# Sheet2.net
KiCad netlist of a schematic drawn in Altium Designer
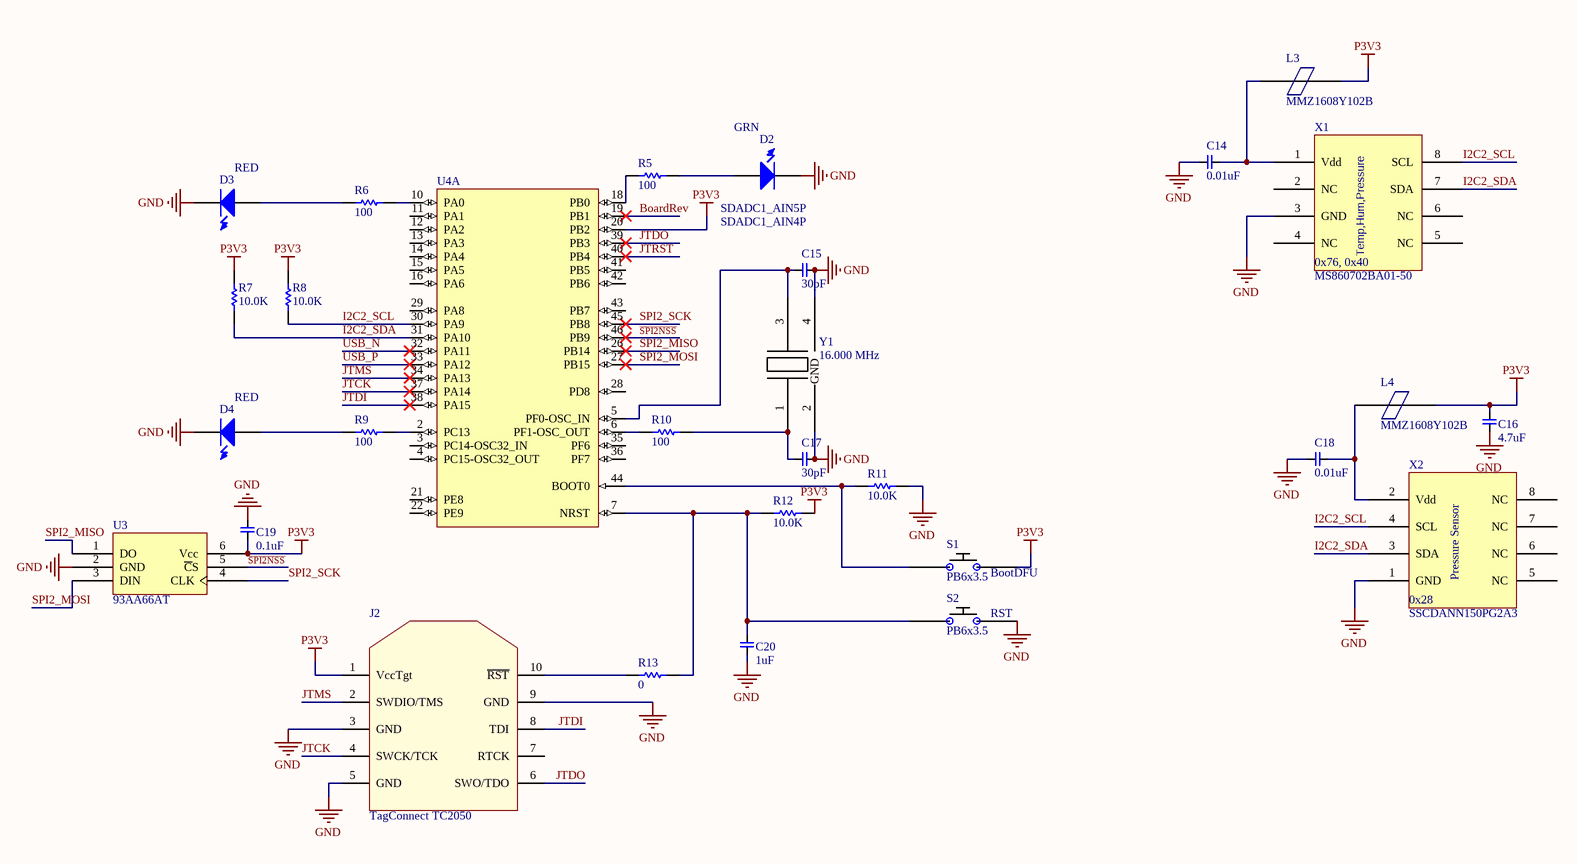
[diagram p0: Sheet2.SchDoc]

(export (version "E")
  (design (tool "Eeschema 10.0.6"))
  (components
    (comp (ref "C14")
      (value "0.01uF")
      (footprint "CAP0402")
      (description "CAP 0.01uF +/-20% 50V X6S 0402")
      (fields (field (name "TOLERANCE") "+/-20%") (field (name "VOLTAGE") "50V"))
      (libsource (lib "PassiveSMT") (part "Capacitor_np"))
    )
    (comp (ref "C15")
      (value "30pF")
      (footprint "CAP0402")
      (description "CAP 30pF +/-5% 50V C0G 0402")
      (fields (field (name "TOLERANCE") "+/-5%") (field (name "VOLTAGE") "50V"))
      (libsource (lib "PassiveSMT") (part "Capacitor_np"))
    )
    (comp (ref "C16")
      (value "4.7uF")
      (footprint "CAP0603")
      (description "CAP 4.7uF +/-10% 10V X6S 0603")
      (fields (field (name "TOLERANCE") "+/-10%") (field (name "VOLTAGE") "10V"))
      (libsource (lib "PassiveSMT") (part "Capacitor_np"))
    )
    (comp (ref "C17")
      (value "30pF")
      (footprint "CAP0402")
      (description "CAP 30pF +/-5% 50V C0G 0402")
      (fields (field (name "TOLERANCE") "+/-5%") (field (name "VOLTAGE") "50V"))
      (libsource (lib "PassiveSMT") (part "Capacitor_np"))
    )
    (comp (ref "C18")
      (value "0.01uF")
      (footprint "CAP0402")
      (description "CAP 0.01uF +/-20% 50V X6S 0402")
      (fields (field (name "TOLERANCE") "+/-20%") (field (name "VOLTAGE") "50V"))
      (libsource (lib "PassiveSMT") (part "Capacitor_np"))
    )
    (comp (ref "C19")
      (value "0.1uF")
      (footprint "CAP0402")
      (description "CAP 0.1uF +/-10% 25V X7R 0402")
      (fields (field (name "TOLERANCE") "+/-10%") (field (name "VOLTAGE") "25V"))
      (libsource (lib "PassiveSMT") (part "Capacitor_np"))
    )
    (comp (ref "C20")
      (value "1uF")
      (footprint "CAP0402")
      (description "CAP 1uF +/-10% 10V X5R 0402")
      (fields (field (name "TOLERANCE") "+/-10%") (field (name "VOLTAGE") "10V"))
      (libsource (lib "PassiveSMT") (part "Capacitor_np"))
    )
    (comp (ref "D2")
      (value "GRN")
      (footprint "KINGBRIGHT_LED")
      (description "LED 1.6X0.8MM 568NM GRN CLR SMD")
      (fields (field (name "MANUFACTURER") "Kingbright"))
      (libsource (lib "MF_MiscLib") (part "LED_GRN_SMD_0603"))
    )
    (comp (ref "D3")
      (value "RED")
      (footprint "KINGBRIGHT_LED")
      (description "LED 1.6X0.8MM 630NM RED CLR SMD")
      (fields (field (name "MANUFACTURER") "Kingbright"))
      (libsource (lib "MF_MiscLib") (part "LED_RED_SMD_0603"))
    )
    (comp (ref "D4")
      (value "RED")
      (footprint "KINGBRIGHT_LED")
      (description "LED 1.6X0.8MM 630NM RED CLR SMD")
      (fields (field (name "MANUFACTURER") "Kingbright"))
      (libsource (lib "MF_MiscLib") (part "LED_RED_SMD_0603"))
    )
    (comp (ref "J2")
      (value "TagConnect TC2050")
      (footprint "TC2050-IDC")
      (description "TagConnect TC2050-IDC For ARM JTAG")
      (fields (field (name "MANUFACTURER") "Tag-Connect LLC"))
      (libsource (lib "MF_MiscLib") (part "TC2050_ARMJTAG"))
    )
    (comp (ref "L3")
      (value "MMZ1608Y102B")
      (footprint "INDC1608X06N")
      (description "Ferrite, 1000oh, 400mA, 0603")
      (libsource (lib "MF_MiscLib") (part "MMZ1608Y102B"))
    )
    (comp (ref "L4")
      (value "MMZ1608Y102B")
      (footprint "INDC1608X06N")
      (description "Ferrite, 1000oh, 400mA, 0603")
      (libsource (lib "MF_MiscLib") (part "MMZ1608Y102B"))
    )
    (comp (ref "R5")
      (value "100")
      (footprint "RES0402")
      (description "Resistor SMT 0402 100 1% ohm")
      (fields (field (name "TOLERANCE") "1%") (field (name "POWER") "1/16W"))
      (libsource (lib "PassiveSMT") (part "Resistor1"))
    )
    (comp (ref "R6")
      (value "100")
      (footprint "RES0402")
      (description "Resistor SMT 0402 100 1% ohm")
      (fields (field (name "TOLERANCE") "1%") (field (name "POWER") "1/16W"))
      (libsource (lib "PassiveSMT") (part "Resistor1"))
    )
    (comp (ref "R7")
      (value "10.0K")
      (footprint "RES0402")
      (description "Resistor SMT 0402 10.0K 1% ohm")
      (fields (field (name "TOLERANCE") "1%") (field (name "POWER") "1/16W"))
      (libsource (lib "PassiveSMT") (part "Resistor1"))
    )
    (comp (ref "R8")
      (value "10.0K")
      (footprint "RES0402")
      (description "Resistor SMT 0402 10.0K 1% ohm")
      (fields (field (name "TOLERANCE") "1%") (field (name "POWER") "1/16W"))
      (libsource (lib "PassiveSMT") (part "Resistor1"))
    )
    (comp (ref "R9")
      (value "100")
      (footprint "RES0402")
      (description "Resistor SMT 0402 100 1% ohm")
      (fields (field (name "TOLERANCE") "1%") (field (name "POWER") "1/16W"))
      (libsource (lib "PassiveSMT") (part "Resistor1"))
    )
    (comp (ref "R10")
      (value "100")
      (footprint "RES0402")
      (description "Resistor SMT 0402 100 1% ohm")
      (fields (field (name "TOLERANCE") "1%") (field (name "POWER") "1/16W"))
      (libsource (lib "PassiveSMT") (part "Resistor1"))
    )
    (comp (ref "R11")
      (value "10.0K")
      (footprint "RES0402")
      (description "Resistor SMT 0402 10.0K 1% ohm")
      (fields (field (name "TOLERANCE") "1%") (field (name "POWER") "1/16W"))
      (libsource (lib "PassiveSMT") (part "Resistor1"))
    )
    (comp (ref "R12")
      (value "10.0K")
      (footprint "RES0402")
      (description "Resistor SMT 0402 10.0K 1% ohm")
      (fields (field (name "TOLERANCE") "1%") (field (name "POWER") "1/16W"))
      (libsource (lib "PassiveSMT") (part "Resistor1"))
    )
    (comp (ref "R13")
      (value "0")
      (footprint "RES0402")
      (description "Resistor SMT 0402 0 1% ohm")
      (fields (field (name "TOLERANCE") "1%") (field (name "POWER") "1/16W"))
      (libsource (lib "PassiveSMT") (part "Resistor1"))
    )
    (comp (ref "S1")
      (value "PB6x3.5")
      (footprint "PTS635")
      (description "SWITCH TACTILE SPST-NO 0.05A 12V 6x3.5MM")
      (fields (field (name "MANUFACTURER") "C&K Components"))
      (libsource (lib "MF_MiscLib") (part "PushButton_6x3.5mm"))
    )
    (comp (ref "S2")
      (value "PB6x3.5")
      (footprint "PTS635")
      (description "SWITCH TACTILE SPST-NO 0.05A 12V 6x3.5MM")
      (fields (field (name "MANUFACTURER") "C&K Components"))
      (libsource (lib "MF_MiscLib") (part "PushButton_6x3.5mm"))
    )
    (comp (ref "U3")
      (value "93AA66AT")
      (footprint "SOT-23-OT6_M")
      (description "IC EEPROM 4KBIT 2MHZ SOT23-6")
      (fields (field (name "MANUFACTURER") "Microchip Technology"))
      (libsource (lib "MF_MiscLib") (part "93AA66AT_SOT23-6"))
    )
    (comp (ref "U4")
      (value "~")
      (footprint "STM-LQFP48_N")
      (fields (field (name "PARTNUMBER") "STM32F373CCT6"))
      (libsource (lib "STMicroelectronics_STM32_F3") (part "STM32F373CCT6"))
    )
    (comp (ref "X1")
      (value "MS860702BA01-50")
      (footprint "TETempHumidityPressSens")
      (description "Humidity, Pressure, Temperature Sensor I²C Output")
      (fields (field (name "MANUFACTURER") "TE Connectivity"))
      (libsource (lib "MF_MiscLib") (part "MS860702BA01-50"))
    )
    (comp (ref "X2")
      (value "SSCDANN150PG2A3")
      (footprint "HoneywellPsenseDIP")
      (description "SENSOR PRES 150PSI GAUG 3.3V DIP I2C")
      (fields (field (name "MANUFACTURER") "Honeywell"))
      (libsource (lib "MF_MiscLib") (part "SSCDANN150PG2A3"))
    )
    (comp (ref "Y1")
      (value "16.000 MHz")
      (footprint "CRYSTAL_SMD_3.2x2.5")
      (description "CRYSTAL 16.0MHZ 20PF,80ohm PARALLEL SMD +/-10PPM")
      (fields (field (name "MANUFACTURER") "CTS-Frequency Controls"))
      (libsource (lib "MF_MiscLib") (part "Crystal_16.00MHz_SMD"))
    )
  )
  (nets
    (net (code "1") (name "/BoardRev") (class "Default")
      (node (ref "U4") (pin "19") (pinfunction "PB1_19") (pintype "bidirectional+no_connect"))
    )
    (net (code "2") (name "/I2C2_SCL") (class "Default")
      (node (ref "R8") (pin "2") (pinfunction "2_2") (pintype "passive"))
      (node (ref "U4") (pin "30") (pinfunction "PA9_30") (pintype "bidirectional"))
      (node (ref "X1") (pin "8") (pinfunction "SCL_8") (pintype "passive"))
      (node (ref "X2") (pin "4") (pinfunction "SCL_4") (pintype "passive"))
    )
    (net (code "3") (name "/I2C2_SDA") (class "Default")
      (node (ref "R7") (pin "2") (pinfunction "2_2") (pintype "passive"))
      (node (ref "U4") (pin "31") (pinfunction "PA10_31") (pintype "bidirectional"))
      (node (ref "X1") (pin "7") (pinfunction "SDA_7") (pintype "passive"))
      (node (ref "X2") (pin "3") (pinfunction "SDA_3") (pintype "passive"))
    )
    (net (code "4") (name "/JTCK") (class "Default")
      (node (ref "J2") (pin "4") (pinfunction "SWCK/TCK_4") (pintype "passive"))
      (node (ref "U4") (pin "37") (pinfunction "PA14_37") (pintype "bidirectional"))
    )
    (net (code "5") (name "/JTDI") (class "Default")
      (node (ref "J2") (pin "8") (pinfunction "TDI_8") (pintype "passive"))
      (node (ref "U4") (pin "38") (pinfunction "PA15_38") (pintype "bidirectional"))
    )
    (net (code "6") (name "/JTDO") (class "Default")
      (node (ref "J2") (pin "6") (pinfunction "SWO/TDO_6") (pintype "passive"))
      (node (ref "U4") (pin "39") (pinfunction "PB3_39") (pintype "bidirectional"))
    )
    (net (code "7") (name "/JTMS") (class "Default")
      (node (ref "J2") (pin "2") (pinfunction "SWDIO/TMS_2") (pintype "passive"))
      (node (ref "U4") (pin "34") (pinfunction "PA13_34") (pintype "bidirectional"))
    )
    (net (code "8") (name "/JTRST") (class "Default")
      (node (ref "U4") (pin "40") (pinfunction "PB4_40") (pintype "bidirectional+no_connect"))
    )
    (net (code "9") (name "/SPI2NSS") (class "Default")
      (node (ref "U3") (pin "5") (pinfunction "~{C}S_5") (pintype "passive"))
      (node (ref "U4") (pin "46") (pinfunction "PB9_46") (pintype "bidirectional"))
    )
    (net (code "10") (name "/SPI2_MISO") (class "Default")
      (node (ref "U3") (pin "1") (pinfunction "DO_1") (pintype "passive"))
      (node (ref "U4") (pin "26") (pinfunction "PB14_26") (pintype "bidirectional"))
    )
    (net (code "11") (name "/SPI2_MOSI") (class "Default")
      (node (ref "U3") (pin "3") (pinfunction "DIN_3") (pintype "passive"))
      (node (ref "U4") (pin "27") (pinfunction "PB15_27") (pintype "bidirectional"))
    )
    (net (code "12") (name "/SPI2_SCK") (class "Default")
      (node (ref "U3") (pin "4") (pinfunction "CLK_4") (pintype "passive"))
      (node (ref "U4") (pin "45") (pinfunction "PB8_45") (pintype "bidirectional"))
    )
    (net (code "13") (name "/USB_N") (class "Default")
      (node (ref "U4") (pin "32") (pinfunction "PA11_32") (pintype "bidirectional+no_connect"))
    )
    (net (code "14") (name "/USB_P") (class "Default")
      (node (ref "U4") (pin "33") (pinfunction "PA12_33") (pintype "bidirectional+no_connect"))
    )
    (net (code "15") (name "GND") (class "Default")
      (node (ref "C14") (pin "2") (pinfunction "2_2") (pintype "passive"))
      (node (ref "C15") (pin "1") (pinfunction "1_1") (pintype "passive"))
      (node (ref "C16") (pin "2") (pinfunction "2_2") (pintype "passive"))
      (node (ref "C17") (pin "1") (pinfunction "1_1") (pintype "passive"))
      (node (ref "C18") (pin "2") (pinfunction "2_2") (pintype "passive"))
      (node (ref "C19") (pin "2") (pinfunction "2_2") (pintype "passive"))
      (node (ref "C20") (pin "1") (pinfunction "1_1") (pintype "passive"))
      (node (ref "D2") (pin "2") (pinfunction "K_2") (pintype "passive"))
      (node (ref "D3") (pin "2") (pinfunction "K_2") (pintype "passive"))
      (node (ref "D4") (pin "2") (pinfunction "K_2") (pintype "passive"))
      (node (ref "J2") (pin "3") (pinfunction "GND_3") (pintype "passive"))
      (node (ref "J2") (pin "5") (pinfunction "GND_5") (pintype "passive"))
      (node (ref "J2") (pin "9") (pinfunction "GND_9") (pintype "passive"))
      (node (ref "R11") (pin "2") (pinfunction "2_2") (pintype "passive"))
      (node (ref "S2") (pin "2") (pinfunction "2_2") (pintype "passive"))
      (node (ref "U3") (pin "2") (pinfunction "GND_2") (pintype "passive"))
      (node (ref "X1") (pin "3") (pinfunction "GND_3") (pintype "passive"))
      (node (ref "X2") (pin "1") (pinfunction "GND_1") (pintype "passive"))
      (node (ref "Y1") (pin "2") (pinfunction "GND_2") (pintype "passive"))
      (node (ref "Y1") (pin "4") (pinfunction "4_4") (pintype "passive"))
    )
    (net (code "16") (name "Net-(C17-Pad2)") (class "Default")
      (node (ref "C17") (pin "2") (pinfunction "2_2") (pintype "passive"))
      (node (ref "R10") (pin "2") (pinfunction "2_2") (pintype "passive"))
      (node (ref "Y1") (pin "1") (pinfunction "1_1") (pintype "passive"))
    )
    (net (code "17") (name "Net-(D2-A)") (class "Default")
      (node (ref "D2") (pin "1") (pinfunction "A_1") (pintype "passive"))
      (node (ref "R5") (pin "2") (pinfunction "2_2") (pintype "passive"))
    )
    (net (code "18") (name "Net-(D3-A)") (class "Default")
      (node (ref "D3") (pin "1") (pinfunction "A_1") (pintype "passive"))
      (node (ref "R6") (pin "1") (pinfunction "1_1") (pintype "passive"))
    )
    (net (code "19") (name "Net-(D4-A)") (class "Default")
      (node (ref "D4") (pin "1") (pinfunction "A_1") (pintype "passive"))
      (node (ref "R9") (pin "1") (pinfunction "1_1") (pintype "passive"))
    )
    (net (code "20") (name "Net-(J2-RST)") (class "Default")
      (node (ref "J2") (pin "10") (pinfunction "RST_10") (pintype "passive"))
      (node (ref "R13") (pin "1") (pinfunction "1_1") (pintype "passive"))
    )
    (net (code "21") (name "Net-(U4A-BOOT0)") (class "Default")
      (node (ref "R11") (pin "1") (pinfunction "1_1") (pintype "passive"))
      (node (ref "S1") (pin "1") (pinfunction "1_1") (pintype "passive"))
      (node (ref "U4") (pin "44") (pinfunction "BOOT0_44") (pintype "input"))
    )
    (net (code "22") (name "Net-(U4A-NRST)") (class "Default")
      (node (ref "C20") (pin "2") (pinfunction "2_2") (pintype "passive"))
      (node (ref "R12") (pin "1") (pinfunction "1_1") (pintype "passive"))
      (node (ref "R13") (pin "2") (pinfunction "2_2") (pintype "passive"))
      (node (ref "S2") (pin "1") (pinfunction "1_1") (pintype "passive"))
      (node (ref "U4") (pin "7") (pinfunction "NRST_7") (pintype "bidirectional"))
    )
    (net (code "23") (name "Net-(U4A-PA0)") (class "Default")
      (node (ref "R6") (pin "2") (pinfunction "2_2") (pintype "passive"))
      (node (ref "U4") (pin "10") (pinfunction "PA0_10") (pintype "bidirectional"))
    )
    (net (code "24") (name "Net-(U4A-PB0)") (class "Default")
      (node (ref "R5") (pin "1") (pinfunction "1_1") (pintype "passive"))
      (node (ref "U4") (pin "18") (pinfunction "PB0_18") (pintype "bidirectional"))
    )
    (net (code "25") (name "Net-(U4A-PC13)") (class "Default")
      (node (ref "R9") (pin "2") (pinfunction "2_2") (pintype "passive"))
      (node (ref "U4") (pin "2") (pinfunction "PC13_2") (pintype "bidirectional"))
    )
    (net (code "26") (name "Net-(U4A-PF0-OSC_IN)") (class "Default")
      (node (ref "C15") (pin "2") (pinfunction "2_2") (pintype "passive"))
      (node (ref "U4") (pin "5") (pinfunction "PF0-OSC_IN_5") (pintype "bidirectional"))
      (node (ref "Y1") (pin "3") (pinfunction "3_3") (pintype "passive"))
    )
    (net (code "27") (name "Net-(U4A-PF1-OSC_OUT)") (class "Default")
      (node (ref "R10") (pin "1") (pinfunction "1_1") (pintype "passive"))
      (node (ref "U4") (pin "6") (pinfunction "PF1-OSC_OUT_6") (pintype "bidirectional"))
    )
    (net (code "28") (name "Net-(X1-Vdd)") (class "Default")
      (node (ref "C14") (pin "1") (pinfunction "1_1") (pintype "passive"))
      (node (ref "L3") (pin "1") (pinfunction "1_1") (pintype "passive"))
      (node (ref "X1") (pin "1") (pinfunction "Vdd_1") (pintype "passive"))
    )
    (net (code "29") (name "Net-(X2-Vdd)") (class "Default")
      (node (ref "C18") (pin "1") (pinfunction "1_1") (pintype "passive"))
      (node (ref "L4") (pin "1") (pinfunction "1_1") (pintype "passive"))
      (node (ref "X2") (pin "2") (pinfunction "Vdd_2") (pintype "passive"))
    )
    (net (code "30") (name "P3V3") (class "Default")
      (node (ref "C16") (pin "1") (pinfunction "1_1") (pintype "passive"))
      (node (ref "C19") (pin "1") (pinfunction "1_1") (pintype "passive"))
      (node (ref "J2") (pin "1") (pinfunction "VccTgt_1") (pintype "passive"))
      (node (ref "L3") (pin "2") (pinfunction "2_2") (pintype "passive"))
      (node (ref "L4") (pin "2") (pinfunction "2_2") (pintype "passive"))
      (node (ref "R12") (pin "2") (pinfunction "2_2") (pintype "passive"))
      (node (ref "R7") (pin "1") (pinfunction "1_1") (pintype "passive"))
      (node (ref "R8") (pin "1") (pinfunction "1_1") (pintype "passive"))
      (node (ref "S1") (pin "2") (pinfunction "2_2") (pintype "passive"))
      (node (ref "U3") (pin "6") (pinfunction "Vcc_6") (pintype "passive"))
      (node (ref "U4") (pin "20") (pinfunction "PB2_20") (pintype "bidirectional"))
    )
    (net (code "31") (name "unconnected-(J2-RTCK-Pad7)") (class "Default")
      (node (ref "J2") (pin "7") (pinfunction "RTCK_7") (pintype "passive"))
    )
    (net (code "32") (name "unconnected-(U4A-PA1-Pad11)") (class "Default")
      (node (ref "U4") (pin "11") (pinfunction "PA1_11") (pintype "bidirectional"))
    )
    (net (code "33") (name "unconnected-(U4A-PA2-Pad12)") (class "Default")
      (node (ref "U4") (pin "12") (pinfunction "PA2_12") (pintype "bidirectional"))
    )
    (net (code "34") (name "unconnected-(U4A-PA3-Pad13)") (class "Default")
      (node (ref "U4") (pin "13") (pinfunction "PA3_13") (pintype "bidirectional"))
    )
    (net (code "35") (name "unconnected-(U4A-PA4-Pad14)") (class "Default")
      (node (ref "U4") (pin "14") (pinfunction "PA4_14") (pintype "bidirectional"))
    )
    (net (code "36") (name "unconnected-(U4A-PA5-Pad15)") (class "Default")
      (node (ref "U4") (pin "15") (pinfunction "PA5_15") (pintype "bidirectional"))
    )
    (net (code "37") (name "unconnected-(U4A-PA6-Pad16)") (class "Default")
      (node (ref "U4") (pin "16") (pinfunction "PA6_16") (pintype "bidirectional"))
    )
    (net (code "38") (name "unconnected-(U4A-PA8-Pad29)") (class "Default")
      (node (ref "U4") (pin "29") (pinfunction "PA8_29") (pintype "bidirectional"))
    )
    (net (code "39") (name "unconnected-(U4A-PB5-Pad41)") (class "Default")
      (node (ref "U4") (pin "41") (pinfunction "PB5_41") (pintype "bidirectional"))
    )
    (net (code "40") (name "unconnected-(U4A-PB6-Pad42)") (class "Default")
      (node (ref "U4") (pin "42") (pinfunction "PB6_42") (pintype "bidirectional"))
    )
    (net (code "41") (name "unconnected-(U4A-PB7-Pad43)") (class "Default")
      (node (ref "U4") (pin "43") (pinfunction "PB7_43") (pintype "bidirectional"))
    )
    (net (code "42") (name "unconnected-(U4A-PC14-OSC32_IN-Pad3)") (class "Default")
      (node (ref "U4") (pin "3") (pinfunction "PC14-OSC32_IN_3") (pintype "bidirectional"))
    )
    (net (code "43") (name "unconnected-(U4A-PC15-OSC32_OUT-Pad4)") (class "Default")
      (node (ref "U4") (pin "4") (pinfunction "PC15-OSC32_OUT_4") (pintype "bidirectional"))
    )
    (net (code "44") (name "unconnected-(U4A-PD8-Pad28)") (class "Default")
      (node (ref "U4") (pin "28") (pinfunction "PD8_28") (pintype "bidirectional"))
    )
    (net (code "45") (name "unconnected-(U4A-PE8-Pad21)") (class "Default")
      (node (ref "U4") (pin "21") (pinfunction "PE8_21") (pintype "bidirectional"))
    )
    (net (code "46") (name "unconnected-(U4A-PE9-Pad22)") (class "Default")
      (node (ref "U4") (pin "22") (pinfunction "PE9_22") (pintype "bidirectional"))
    )
    (net (code "47") (name "unconnected-(U4A-PF6-Pad35)") (class "Default")
      (node (ref "U4") (pin "35") (pinfunction "PF6_35") (pintype "bidirectional"))
    )
    (net (code "48") (name "unconnected-(U4A-PF7-Pad36)") (class "Default")
      (node (ref "U4") (pin "36") (pinfunction "PF7_36") (pintype "bidirectional"))
    )
    (net (code "49") (name "unconnected-(X1-NC-Pad2)") (class "Default")
      (node (ref "X1") (pin "2") (pinfunction "NC_2") (pintype "passive"))
    )
    (net (code "50") (name "unconnected-(X1-NC-Pad4)") (class "Default")
      (node (ref "X1") (pin "4") (pinfunction "NC_4") (pintype "passive"))
    )
    (net (code "51") (name "unconnected-(X1-NC-Pad5)") (class "Default")
      (node (ref "X1") (pin "5") (pinfunction "NC_5") (pintype "passive"))
    )
    (net (code "52") (name "unconnected-(X1-NC-Pad6)") (class "Default")
      (node (ref "X1") (pin "6") (pinfunction "NC_6") (pintype "passive"))
    )
    (net (code "53") (name "unconnected-(X2-NC-Pad5)") (class "Default")
      (node (ref "X2") (pin "5") (pinfunction "NC_5") (pintype "passive"))
    )
    (net (code "54") (name "unconnected-(X2-NC-Pad6)") (class "Default")
      (node (ref "X2") (pin "6") (pinfunction "NC_6") (pintype "passive"))
    )
    (net (code "55") (name "unconnected-(X2-NC-Pad7)") (class "Default")
      (node (ref "X2") (pin "7") (pinfunction "NC_7") (pintype "passive"))
    )
    (net (code "56") (name "unconnected-(X2-NC-Pad8)") (class "Default")
      (node (ref "X2") (pin "8") (pinfunction "NC_8") (pintype "passive"))
    )
  )
)
